# HamamatsuSensorBoard.net
KiCad netlist of a schematic drawn in Altium Designer
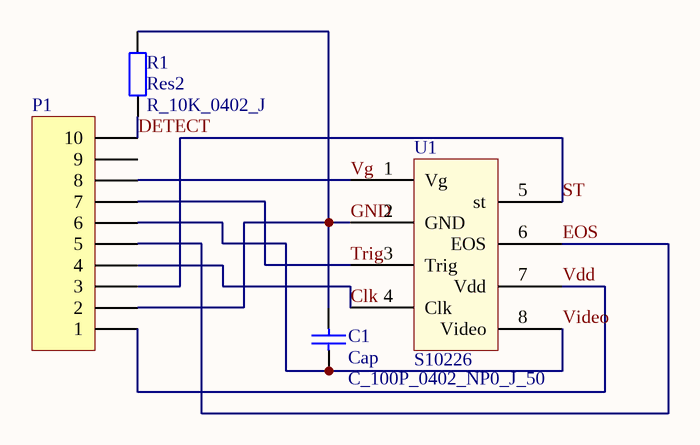
[diagram p0: HamamatsuSensorBoard.SchDoc]

(export (version "E")
  (design (tool "Eeschema 10.0.6"))
  (components
    (comp (ref "C1")
      (value "Cap")
      (footprint "C_0402")
      (description "Capacitor")
      (fields
        (field (name "ALTIUM_VALUE") "C_100P_0402_NP0_J_50")
        (field (name "PUBLISHER") "Altium Limited")
      )
      (libsource (lib "Miscellaneous Devices") (part "Cap"))
    )
    (comp (ref "P1")
      (value "Header 10")
      (footprint "609-4377-ND")
      (description "Header, 10-Pin")
      (fields (field (name "PUBLISHER") "Altium Limited"))
      (libsource (lib "Miscellaneous Connectors") (part "Header 10"))
    )
    (comp (ref "R1")
      (value "Res2")
      (footprint "R_0402")
      (description "Resistor")
      (fields (field (name "ALTIUM_VALUE") "R_10K_0402_J") (field (name "PUBLISHER") "Altium Limited"))
      (libsource (lib "Miscellaneous Devices") (part "Res2"))
    )
    (comp (ref "U1")
      (value "S10226")
      (footprint "S10226")
      (description "Hamamatsu 1024 CMOS image sensor")
      (libsource (lib "BrewBit") (part "S10226"))
    )
  )
  (nets
    (net (code "1") (name "/Clk") (class "Default")
      (node (ref "P1") (pin "4") (pinfunction "4_4") (pintype "passive"))
      (node (ref "U1") (pin "4") (pinfunction "Clk_4") (pintype "passive"))
    )
    (net (code "2") (name "/DETECT") (class "Default")
      (node (ref "P1") (pin "10") (pinfunction "10_10") (pintype "passive"))
      (node (ref "R1") (pin "1") (pinfunction "1_1") (pintype "passive"))
    )
    (net (code "3") (name "/EOS") (class "Default")
      (node (ref "P1") (pin "5") (pinfunction "5_5") (pintype "passive"))
      (node (ref "U1") (pin "6") (pinfunction "EOS_6") (pintype "passive"))
    )
    (net (code "4") (name "/GND") (class "Default")
      (node (ref "C1") (pin "2") (pinfunction "GND_2") (pintype "passive"))
      (node (ref "P1") (pin "2") (pinfunction "2_2") (pintype "passive"))
      (node (ref "R1") (pin "2") (pinfunction "2_2") (pintype "passive"))
      (node (ref "U1") (pin "2") (pinfunction "GND_2") (pintype "passive"))
    )
    (net (code "5") (name "/ST") (class "Default")
      (node (ref "P1") (pin "3") (pinfunction "3_3") (pintype "passive"))
      (node (ref "U1") (pin "5") (pinfunction "st_5") (pintype "passive"))
    )
    (net (code "6") (name "/Trig") (class "Default")
      (node (ref "P1") (pin "7") (pinfunction "7_7") (pintype "passive"))
      (node (ref "U1") (pin "3") (pinfunction "Trig_3") (pintype "passive"))
    )
    (net (code "7") (name "/Vdd") (class "Default")
      (node (ref "P1") (pin "1") (pinfunction "1_1") (pintype "passive"))
      (node (ref "U1") (pin "7") (pinfunction "Vdd_7") (pintype "passive"))
    )
    (net (code "8") (name "/Vg") (class "Default")
      (node (ref "P1") (pin "8") (pinfunction "8_8") (pintype "passive"))
      (node (ref "U1") (pin "1") (pinfunction "Vg_1") (pintype "passive"))
    )
    (net (code "9") (name "/Video") (class "Default")
      (node (ref "C1") (pin "1") (pinfunction "Vdd_1") (pintype "passive"))
      (node (ref "P1") (pin "6") (pinfunction "6_6") (pintype "passive"))
      (node (ref "U1") (pin "8") (pinfunction "Video_8") (pintype "passive"))
    )
    (net (code "10") (name "unconnected-(P1-Pad9)") (class "Default")
      (node (ref "P1") (pin "9") (pinfunction "9_9") (pintype "passive"))
    )
  )
)
